# RC_Transmitter_RX_FINAL_v42.net
KiCad netlist of a schematic drawn in EAGLE
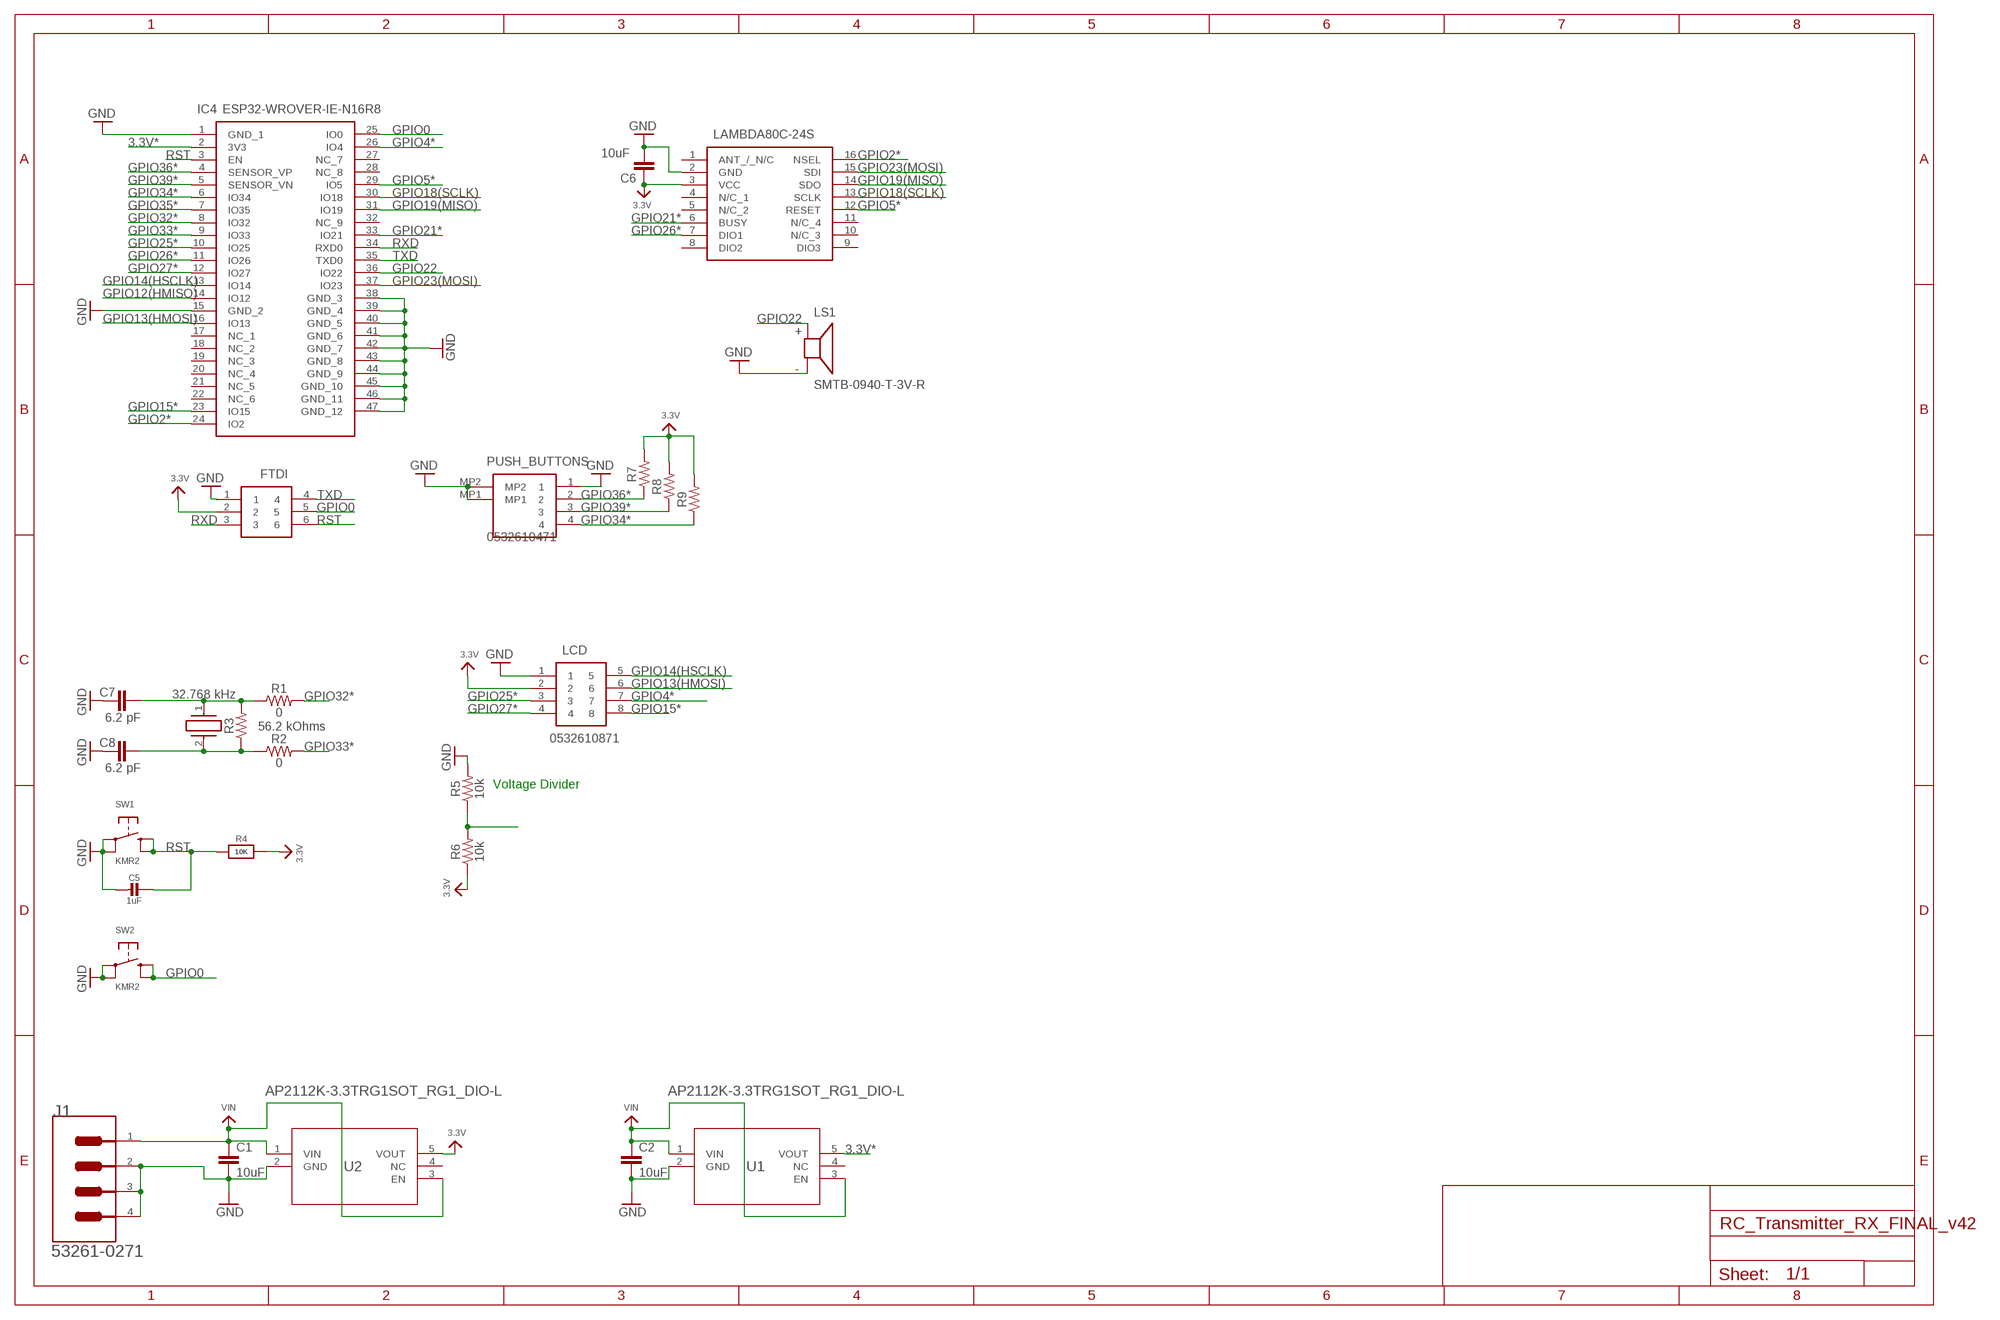
[diagram p0: schematic, sheet 1]

(export (version "E")
  (design (tool "Eeschema 10.0.6"))
  (components
    (comp (ref "C1")
      (value "10uF")
      (footprint "eagle-import:0805")
      (libsource (lib "eagle-import") (part "10UF-0805-10V-10%"))
    )
    (comp (ref "C2")
      (value "10uF")
      (footprint "eagle-import:0805")
      (libsource (lib "eagle-import") (part "10UF-0805-10V-10%"))
    )
    (comp (ref "C5")
      (value "1uF")
      (footprint "eagle-import:0805-NO")
      (libsource (lib "eagle-import") (part "CAP_CERAMIC0805-NOOUTLINE"))
    )
    (comp (ref "C6")
      (value "10uF")
      (footprint "eagle-import:0805")
      (libsource (lib "eagle-import") (part "10UF-0805-10V-10%"))
    )
    (comp (ref "C7")
      (value "6.2 pF")
      (footprint "eagle-import:CAPC2012X110")
      (libsource (lib "eagle-import") (part "CCHIP-0805(2012-METRIC)_"))
    )
    (comp (ref "C8")
      (value "6.2 pF")
      (footprint "eagle-import:CAPC2012X110")
      (libsource (lib "eagle-import") (part "CCHIP-0805(2012-METRIC)_"))
    )
    (comp (ref "CRYSTAL")
      (value "32.768 kHz")
      (footprint "eagle-import:ECX327CDX1293")
      (fields
        (field (name "ARROW_PART_NUMBER") "ECX-.327-CDX-1293")
        (field (name "MOUSER_PART_NUMBER") "520-ECX-.327CDX-1293")
        (field (name "ARROW_PART_NUMBER_1") "Crystal")
      )
      (libsource (lib "eagle-import") (part "ECX-.327-CDX-1293"))
    )
    (comp (ref "FTDI")
      (value "0532610671")
      (footprint "eagle-import:0532610671")
      (libsource (lib "eagle-import") (part "0532610671"))
    )
    (comp (ref "IC1")
      (value "LAMBDA80C-24S")
      (footprint "eagle-import:LAMBDA80C24S")
      (fields (field (name "MOUSER_PART_NUMBER") "223-LAMBDA80C-24S"))
      (libsource (lib "eagle-import") (part "LAMBDA80C-24S"))
    )
    (comp (ref "IC4")
      (value "ESP32-WROVER-IE-N16R8")
      (footprint "eagle-import:ESP32WROVERIEN16R8")
      (fields
        (field (name "MANUFACTURER_PART_NUMBER") "ESP32-Wrover-IE-N16R8")
        (field (name "MOUSER_PART_NUMBER") "356-ESP32WRVIE2864UC")
      )
      (libsource (lib "eagle-import") (part "ESP32-WROVER-IE-N16R8"))
    )
    (comp (ref "J1")
      (value "MOLEX_53261-0271MOLEX_53261-0271_0_0")
      (footprint "eagle-import:MOLEX_53261-0271_0")
      (fields
        (field (name "DIGIKEY_PART_NUMBER") "WM7620CT-ND")
        (field (name "MF") "Molex")
        (field (name "MOUSER_PART_NUMBER") "538-53261-0271")
      )
      (libsource (lib "eagle-import") (part "MOLEX_53261-0271MOLEX_53261-0271_0_0"))
    )
    (comp (ref "LCD")
      (value "0532610871")
      (footprint "eagle-import:53261-0871")
      (libsource (lib "eagle-import") (part "0532610871"))
    )
    (comp (ref "LS1")
      (value "SMTB-0940-T-3V-R")
      (footprint "eagle-import:XDCR_SMTB-0940-T-3V-R")
      (fields (field (name "MF") "PUI Audio, Inc."))
      (libsource (lib "eagle-import") (part "SMTB-0940-T-3V-R"))
    )
    (comp (ref "PUSH_BUTTONS")
      (value "0532610471")
      (footprint "eagle-import:0532610471")
      (libsource (lib "eagle-import") (part "0532610471"))
    )
    (comp (ref "R1")
      (value "0")
      (footprint "eagle-import:0603")
      (libsource (lib "eagle-import") (part "0OHM-0603-1/10W-5%"))
    )
    (comp (ref "R2")
      (value "0")
      (footprint "eagle-import:0603")
      (libsource (lib "eagle-import") (part "0OHM-0603-1/10W-5%"))
    )
    (comp (ref "R3")
      (value "56.2 kOhms")
      (footprint "eagle-import:0603")
      (libsource (lib "eagle-import") (part "0OHM-0603-1/10W-5%"))
    )
    (comp (ref "R4")
      (value "10K")
      (footprint "eagle-import:_0805")
      (libsource (lib "eagle-import") (part "RESISTOR_0805"))
    )
    (comp (ref "R5")
      (value "10k")
      (footprint "eagle-import:0603")
      (libsource (lib "eagle-import") (part "0OHM-0603-1/10W-5%"))
    )
    (comp (ref "R6")
      (value "10k")
      (footprint "eagle-import:0603")
      (libsource (lib "eagle-import") (part "0OHM-0603-1/10W-5%"))
    )
    (comp (ref "R7")
      (value "0")
      (footprint "eagle-import:0603")
      (libsource (lib "eagle-import") (part "0OHM-0603-1/10W-5%"))
    )
    (comp (ref "R8")
      (value "0")
      (footprint "eagle-import:0603")
      (libsource (lib "eagle-import") (part "0OHM-0603-1/10W-5%"))
    )
    (comp (ref "R9")
      (value "0")
      (footprint "eagle-import:0603")
      (libsource (lib "eagle-import") (part "0OHM-0603-1/10W-5%"))
    )
    (comp (ref "SW1")
      (value "KMR2")
      (footprint "eagle-import:BTN_KMR2_4.6X2.8")
      (libsource (lib "eagle-import") (part "SWITCH_TACT_SMT4.6X2.8"))
    )
    (comp (ref "SW2")
      (value "KMR2")
      (footprint "eagle-import:BTN_KMR2_4.6X2.8")
      (libsource (lib "eagle-import") (part "SWITCH_TACT_SMT4.6X2.8"))
    )
    (comp (ref "U1")
      (value "AP2112K-3.3TRG1SOT_RG1_DIO-L")
      (footprint "eagle-import:SOT_RG1_DIO-L")
      (fields
        (field (name "MANUFACTURER_PART_NUMBER") "AP2112K-3.3TRG1")
        (field (name "COPYRIGHT") "Copyright (C) 2023 Ultra Librarian. All rights reserved.")
      )
      (libsource (lib "eagle-import") (part "AP2112K-3.3TRG1SOT_RG1_DIO-L"))
    )
    (comp (ref "U2")
      (value "AP2112K-3.3TRG1SOT_RG1_DIO-L")
      (footprint "eagle-import:SOT_RG1_DIO-L")
      (fields
        (field (name "MANUFACTURER_PART_NUMBER") "AP2112K-3.3TRG1")
        (field (name "COPYRIGHT") "Copyright (C) 2023 Ultra Librarian. All rights reserved.")
      )
      (libsource (lib "eagle-import") (part "AP2112K-3.3TRG1SOT_RG1_DIO-L"))
    )
  )
  (nets
    (net (code "1") (name "/3.3V*") (class "Default")
      (node (ref "IC4") (pin "2") (pinfunction "3V3_2") (pintype "bidirectional"))
      (node (ref "U1") (pin "5") (pinfunction "VOUT_5") (pintype "passive"))
    )
    (net (code "2") (name "/GPIO0") (class "Default")
      (node (ref "FTDI") (pin "5") (pinfunction "5_5") (pintype "bidirectional"))
      (node (ref "IC4") (pin "25") (pinfunction "IO0_25") (pintype "bidirectional"))
      (node (ref "SW2") (pin "B") (pinfunction "S_B") (pintype "passive"))
      (node (ref "SW2") (pin "B'") (pinfunction "S1_B'") (pintype "passive"))
    )
    (net (code "3") (name "/GPIO2*") (class "Default")
      (node (ref "IC1") (pin "16") (pinfunction "NSEL_16") (pintype "bidirectional"))
      (node (ref "IC4") (pin "24") (pinfunction "IO2_24") (pintype "bidirectional"))
    )
    (net (code "4") (name "/GPIO4*") (class "Default")
      (node (ref "IC4") (pin "26") (pinfunction "IO4_26") (pintype "bidirectional"))
      (node (ref "LCD") (pin "7") (pinfunction "7_7") (pintype "bidirectional"))
    )
    (net (code "5") (name "/GPIO5*") (class "Default")
      (node (ref "IC1") (pin "12") (pinfunction "RESET_12") (pintype "bidirectional"))
      (node (ref "IC4") (pin "29") (pinfunction "IO5_29") (pintype "bidirectional"))
    )
    (net (code "6") (name "/GPIO12(HMISO)") (class "Default")
      (node (ref "IC4") (pin "14") (pinfunction "IO12_14") (pintype "bidirectional"))
    )
    (net (code "7") (name "/GPIO13(HMOSI)") (class "Default")
      (node (ref "IC4") (pin "16") (pinfunction "IO13_16") (pintype "bidirectional"))
      (node (ref "LCD") (pin "6") (pinfunction "6_6") (pintype "bidirectional"))
    )
    (net (code "8") (name "/GPIO14(HSCLK)") (class "Default")
      (node (ref "IC4") (pin "13") (pinfunction "IO14_13") (pintype "bidirectional"))
      (node (ref "LCD") (pin "5") (pinfunction "5_5") (pintype "bidirectional"))
    )
    (net (code "9") (name "/GPIO15*") (class "Default")
      (node (ref "IC4") (pin "23") (pinfunction "IO15_23") (pintype "bidirectional"))
      (node (ref "LCD") (pin "8") (pinfunction "8_8") (pintype "bidirectional"))
    )
    (net (code "10") (name "/GPIO18(SCLK)") (class "Default")
      (node (ref "IC1") (pin "13") (pinfunction "SCLK_13") (pintype "bidirectional"))
      (node (ref "IC4") (pin "30") (pinfunction "IO18_30") (pintype "bidirectional"))
    )
    (net (code "11") (name "/GPIO19(MISO)") (class "Default")
      (node (ref "IC1") (pin "14") (pinfunction "SDO_14") (pintype "bidirectional"))
      (node (ref "IC4") (pin "31") (pinfunction "IO19_31") (pintype "bidirectional"))
    )
    (net (code "12") (name "/GPIO21*") (class "Default")
      (node (ref "IC1") (pin "6") (pinfunction "BUSY_6") (pintype "bidirectional"))
      (node (ref "IC4") (pin "33") (pinfunction "IO21_33") (pintype "bidirectional"))
    )
    (net (code "13") (name "/GPIO22") (class "Default")
      (node (ref "IC4") (pin "36") (pinfunction "IO22_36") (pintype "bidirectional"))
      (node (ref "LS1") (pin "P") (pinfunction "P_P") (pintype "passive"))
    )
    (net (code "14") (name "/GPIO23(MOSI)") (class "Default")
      (node (ref "IC1") (pin "15") (pinfunction "SDI_15") (pintype "bidirectional"))
      (node (ref "IC4") (pin "37") (pinfunction "IO23_37") (pintype "bidirectional"))
    )
    (net (code "15") (name "/GPIO25*") (class "Default")
      (node (ref "IC4") (pin "10") (pinfunction "IO25_10") (pintype "bidirectional"))
      (node (ref "LCD") (pin "3") (pinfunction "3_3") (pintype "bidirectional"))
    )
    (net (code "16") (name "/GPIO26*") (class "Default")
      (node (ref "IC1") (pin "7") (pinfunction "DIO1_7") (pintype "bidirectional"))
      (node (ref "IC4") (pin "11") (pinfunction "IO26_11") (pintype "bidirectional"))
    )
    (net (code "17") (name "/GPIO27*") (class "Default")
      (node (ref "IC4") (pin "12") (pinfunction "IO27_12") (pintype "bidirectional"))
      (node (ref "LCD") (pin "4") (pinfunction "4_4") (pintype "bidirectional"))
    )
    (net (code "18") (name "/GPIO32*") (class "Default")
      (node (ref "IC4") (pin "8") (pinfunction "IO32_8") (pintype "bidirectional"))
      (node (ref "R1") (pin "2") (pinfunction "2_2") (pintype "passive"))
    )
    (net (code "19") (name "/GPIO33*") (class "Default")
      (node (ref "IC4") (pin "9") (pinfunction "IO33_9") (pintype "bidirectional"))
      (node (ref "R2") (pin "2") (pinfunction "2_2") (pintype "passive"))
    )
    (net (code "20") (name "/GPIO34*") (class "Default")
      (node (ref "IC4") (pin "6") (pinfunction "IO34_6") (pintype "bidirectional"))
      (node (ref "PUSH_BUTTONS") (pin "4") (pinfunction "4_4") (pintype "bidirectional"))
      (node (ref "R9") (pin "1") (pinfunction "1_1") (pintype "passive"))
    )
    (net (code "21") (name "/GPIO35*") (class "Default")
      (node (ref "IC4") (pin "7") (pinfunction "IO35_7") (pintype "bidirectional"))
      (node (ref "R5") (pin "1") (pinfunction "1_1") (pintype "passive"))
      (node (ref "R6") (pin "2") (pinfunction "2_2") (pintype "passive"))
    )
    (net (code "22") (name "/GPIO36*") (class "Default")
      (node (ref "IC4") (pin "4") (pinfunction "SENSOR_VP_4") (pintype "bidirectional"))
      (node (ref "PUSH_BUTTONS") (pin "2") (pinfunction "2_2") (pintype "bidirectional"))
      (node (ref "R7") (pin "1") (pinfunction "1_1") (pintype "passive"))
    )
    (net (code "23") (name "/GPIO39*") (class "Default")
      (node (ref "IC4") (pin "5") (pinfunction "SENSOR_VN_5") (pintype "bidirectional"))
      (node (ref "PUSH_BUTTONS") (pin "3") (pinfunction "3_3") (pintype "bidirectional"))
      (node (ref "R8") (pin "1") (pinfunction "1_1") (pintype "passive"))
    )
    (net (code "24") (name "/RST") (class "Default")
      (node (ref "C5") (pin "1") (pinfunction "1_1") (pintype "passive"))
      (node (ref "FTDI") (pin "6") (pinfunction "6_6") (pintype "bidirectional"))
      (node (ref "IC4") (pin "3") (pinfunction "EN_3") (pintype "bidirectional"))
      (node (ref "R4") (pin "1") (pinfunction "1_1") (pintype "passive"))
      (node (ref "SW1") (pin "B") (pinfunction "S_B") (pintype "passive"))
      (node (ref "SW1") (pin "B'") (pinfunction "S1_B'") (pintype "passive"))
    )
    (net (code "25") (name "/RXD") (class "Default")
      (node (ref "FTDI") (pin "3") (pinfunction "3_3") (pintype "bidirectional"))
      (node (ref "IC4") (pin "34") (pinfunction "RXD0_34") (pintype "bidirectional"))
    )
    (net (code "26") (name "/TXD") (class "Default")
      (node (ref "FTDI") (pin "4") (pinfunction "4_4") (pintype "bidirectional"))
      (node (ref "IC4") (pin "35") (pinfunction "TXD0_35") (pintype "bidirectional"))
    )
    (net (code "27") (name "3.3V") (class "Default")
      (node (ref "C6") (pin "1") (pinfunction "1_1") (pintype "passive"))
      (node (ref "FTDI") (pin "2") (pinfunction "2_2") (pintype "bidirectional"))
      (node (ref "IC1") (pin "3") (pinfunction "VCC_3") (pintype "bidirectional"))
      (node (ref "LCD") (pin "2") (pinfunction "2_2") (pintype "bidirectional"))
      (node (ref "R4") (pin "2") (pinfunction "2_2") (pintype "passive"))
      (node (ref "R6") (pin "1") (pinfunction "1_1") (pintype "passive"))
      (node (ref "R7") (pin "2") (pinfunction "2_2") (pintype "passive"))
      (node (ref "R8") (pin "2") (pinfunction "2_2") (pintype "passive"))
      (node (ref "R9") (pin "2") (pinfunction "2_2") (pintype "passive"))
      (node (ref "U2") (pin "5") (pinfunction "VOUT_5") (pintype "passive"))
    )
    (net (code "28") (name "GND") (class "Default")
      (node (ref "C1") (pin "2") (pinfunction "2_2") (pintype "passive"))
      (node (ref "C2") (pin "2") (pinfunction "2_2") (pintype "passive"))
      (node (ref "C5") (pin "2") (pinfunction "2_2") (pintype "passive"))
      (node (ref "C6") (pin "2") (pinfunction "2_2") (pintype "passive"))
      (node (ref "C7") (pin "1") (pinfunction "1_1") (pintype "passive"))
      (node (ref "C8") (pin "1") (pinfunction "1_1") (pintype "passive"))
      (node (ref "FTDI") (pin "1") (pinfunction "1_1") (pintype "bidirectional"))
      (node (ref "IC1") (pin "2") (pinfunction "GND_2") (pintype "bidirectional"))
      (node (ref "IC4") (pin "1") (pinfunction "GND_1_1") (pintype "bidirectional"))
      (node (ref "IC4") (pin "15") (pinfunction "GND_2_15") (pintype "bidirectional"))
      (node (ref "IC4") (pin "38") (pinfunction "GND_3_38") (pintype "bidirectional"))
      (node (ref "IC4") (pin "39") (pinfunction "GND_4_39") (pintype "bidirectional"))
      (node (ref "IC4") (pin "40") (pinfunction "GND_5_40") (pintype "bidirectional"))
      (node (ref "IC4") (pin "41") (pinfunction "GND_6_41") (pintype "bidirectional"))
      (node (ref "IC4") (pin "42") (pinfunction "GND_7_42") (pintype "bidirectional"))
      (node (ref "IC4") (pin "43") (pinfunction "GND_8_43") (pintype "bidirectional"))
      (node (ref "IC4") (pin "44") (pinfunction "GND_9_44") (pintype "bidirectional"))
      (node (ref "IC4") (pin "45") (pinfunction "GND_10_45") (pintype "bidirectional"))
      (node (ref "IC4") (pin "46") (pinfunction "GND_11_46") (pintype "bidirectional"))
      (node (ref "IC4") (pin "47") (pinfunction "GND_12_47") (pintype "bidirectional"))
      (node (ref "J1") (pin "2") (pinfunction "2_2") (pintype "bidirectional"))
      (node (ref "J1") (pin "3") (pinfunction "MNT_1_3") (pintype "bidirectional"))
      (node (ref "J1") (pin "4") (pinfunction "MNT_2_4") (pintype "bidirectional"))
      (node (ref "LCD") (pin "1") (pinfunction "1_1") (pintype "bidirectional"))
      (node (ref "LS1") (pin "N") (pinfunction "N_N") (pintype "passive"))
      (node (ref "PUSH_BUTTONS") (pin "1") (pinfunction "1_1") (pintype "bidirectional"))
      (node (ref "PUSH_BUTTONS") (pin "MP1") (pinfunction "MP1_MP1") (pintype "bidirectional"))
      (node (ref "PUSH_BUTTONS") (pin "MP2") (pinfunction "MP2_MP2") (pintype "bidirectional"))
      (node (ref "R5") (pin "2") (pinfunction "2_2") (pintype "passive"))
      (node (ref "SW1") (pin "A") (pinfunction "P_A") (pintype "passive"))
      (node (ref "SW1") (pin "A'") (pinfunction "P1_A'") (pintype "passive"))
      (node (ref "SW2") (pin "A") (pinfunction "P_A") (pintype "passive"))
      (node (ref "SW2") (pin "A'") (pinfunction "P1_A'") (pintype "passive"))
      (node (ref "U1") (pin "2") (pinfunction "GND_2") (pintype "passive"))
      (node (ref "U2") (pin "2") (pinfunction "GND_2") (pintype "passive"))
    )
    (net (code "29") (name "Net-(CRYSTAL-X1)") (class "Default")
      (node (ref "C7") (pin "2") (pinfunction "2_2") (pintype "passive"))
      (node (ref "CRYSTAL") (pin "1") (pinfunction "X1_1") (pintype "bidirectional"))
      (node (ref "R1") (pin "1") (pinfunction "1_1") (pintype "passive"))
      (node (ref "R3") (pin "2") (pinfunction "2_2") (pintype "passive"))
    )
    (net (code "30") (name "Net-(CRYSTAL-X2)") (class "Default")
      (node (ref "C8") (pin "2") (pinfunction "2_2") (pintype "passive"))
      (node (ref "CRYSTAL") (pin "2") (pinfunction "X2_2") (pintype "bidirectional"))
      (node (ref "R2") (pin "1") (pinfunction "1_1") (pintype "passive"))
      (node (ref "R3") (pin "1") (pinfunction "1_1") (pintype "passive"))
    )
    (net (code "31") (name "VIN") (class "Default")
      (node (ref "C1") (pin "1") (pinfunction "1_1") (pintype "passive"))
      (node (ref "C2") (pin "1") (pinfunction "1_1") (pintype "passive"))
      (node (ref "J1") (pin "1") (pinfunction "1_1") (pintype "bidirectional"))
      (node (ref "U1") (pin "1") (pinfunction "VIN_1") (pintype "passive"))
      (node (ref "U1") (pin "3") (pinfunction "EN_3") (pintype "passive"))
      (node (ref "U2") (pin "1") (pinfunction "VIN_1") (pintype "passive"))
      (node (ref "U2") (pin "3") (pinfunction "EN_3") (pintype "passive"))
    )
    (net (code "32") (name "unconnected-(IC1-ANT_{slash}_N{slash}C-Pad1)") (class "Default")
      (node (ref "IC1") (pin "1") (pinfunction "ANT_/_N/C_1") (pintype "bidirectional"))
    )
    (net (code "33") (name "unconnected-(IC1-DIO2-Pad8)") (class "Default")
      (node (ref "IC1") (pin "8") (pinfunction "DIO2_8") (pintype "bidirectional"))
    )
    (net (code "34") (name "unconnected-(IC1-DIO3-Pad9)") (class "Default")
      (node (ref "IC1") (pin "9") (pinfunction "DIO3_9") (pintype "bidirectional"))
    )
    (net (code "35") (name "unconnected-(IC1-N{slash}C_1-Pad4)") (class "Default")
      (node (ref "IC1") (pin "4") (pinfunction "N/C_1_4") (pintype "bidirectional"))
    )
    (net (code "36") (name "unconnected-(IC1-N{slash}C_2-Pad5)") (class "Default")
      (node (ref "IC1") (pin "5") (pinfunction "N/C_2_5") (pintype "bidirectional"))
    )
    (net (code "37") (name "unconnected-(IC1-N{slash}C_3-Pad10)") (class "Default")
      (node (ref "IC1") (pin "10") (pinfunction "N/C_3_10") (pintype "bidirectional"))
    )
    (net (code "38") (name "unconnected-(IC1-N{slash}C_4-Pad11)") (class "Default")
      (node (ref "IC1") (pin "11") (pinfunction "N/C_4_11") (pintype "bidirectional"))
    )
    (net (code "39") (name "unconnected-(IC4-NC_1-Pad17)") (class "Default")
      (node (ref "IC4") (pin "17") (pinfunction "NC_1_17") (pintype "bidirectional"))
    )
    (net (code "40") (name "unconnected-(IC4-NC_2-Pad18)") (class "Default")
      (node (ref "IC4") (pin "18") (pinfunction "NC_2_18") (pintype "bidirectional"))
    )
    (net (code "41") (name "unconnected-(IC4-NC_3-Pad19)") (class "Default")
      (node (ref "IC4") (pin "19") (pinfunction "NC_3_19") (pintype "bidirectional"))
    )
    (net (code "42") (name "unconnected-(IC4-NC_4-Pad20)") (class "Default")
      (node (ref "IC4") (pin "20") (pinfunction "NC_4_20") (pintype "bidirectional"))
    )
    (net (code "43") (name "unconnected-(IC4-NC_5-Pad21)") (class "Default")
      (node (ref "IC4") (pin "21") (pinfunction "NC_5_21") (pintype "bidirectional"))
    )
    (net (code "44") (name "unconnected-(IC4-NC_6-Pad22)") (class "Default")
      (node (ref "IC4") (pin "22") (pinfunction "NC_6_22") (pintype "bidirectional"))
    )
    (net (code "45") (name "unconnected-(IC4-NC_7-Pad27)") (class "Default")
      (node (ref "IC4") (pin "27") (pinfunction "NC_7_27") (pintype "bidirectional"))
    )
    (net (code "46") (name "unconnected-(IC4-NC_8-Pad28)") (class "Default")
      (node (ref "IC4") (pin "28") (pinfunction "NC_8_28") (pintype "bidirectional"))
    )
    (net (code "47") (name "unconnected-(IC4-NC_9-Pad32)") (class "Default")
      (node (ref "IC4") (pin "32") (pinfunction "NC_9_32") (pintype "bidirectional"))
    )
    (net (code "48") (name "unconnected-(U1-NC-Pad4)") (class "Default")
      (node (ref "U1") (pin "4") (pinfunction "NC_4") (pintype "passive"))
    )
    (net (code "49") (name "unconnected-(U2-NC-Pad4)") (class "Default")
      (node (ref "U2") (pin "4") (pinfunction "NC_4") (pintype "passive"))
    )
  )
)
